# rotary_breakout.net
KiCad netlist of a schematic drawn in EAGLE
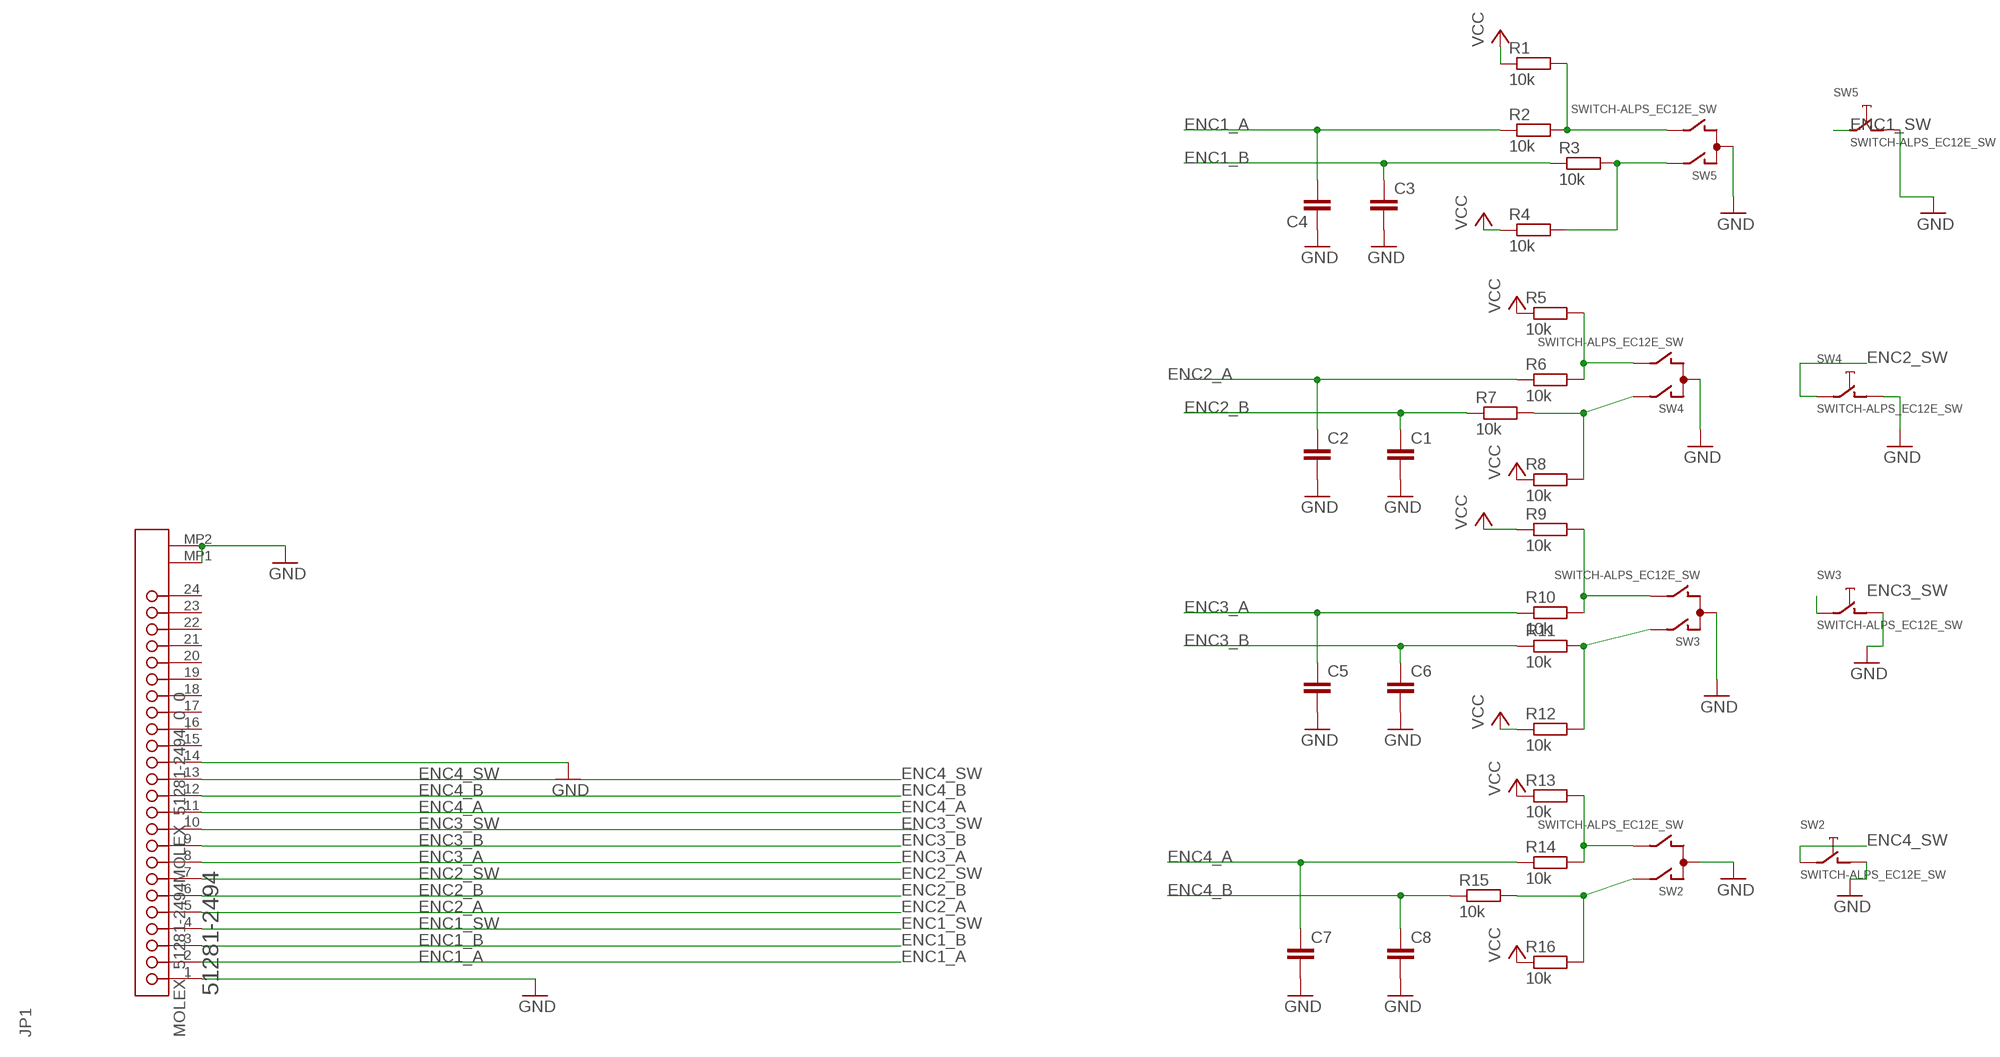
[diagram p0: schematic, sheet 1]

(export (version "E")
  (design (tool "Eeschema 10.0.6"))
  (components
    (comp (ref "C1")
      (value "C-EUC0805")
      (footprint "eagle-import:C0805")
      (libsource (lib "eagle-import") (part "C-EUC0805"))
    )
    (comp (ref "C2")
      (value "C-EUC0805")
      (footprint "eagle-import:C0805")
      (libsource (lib "eagle-import") (part "C-EUC0805"))
    )
    (comp (ref "C3")
      (value "C-EUC0805")
      (footprint "eagle-import:C0805")
      (libsource (lib "eagle-import") (part "C-EUC0805"))
    )
    (comp (ref "C4")
      (value "C-EUC0805")
      (footprint "eagle-import:C0805")
      (libsource (lib "eagle-import") (part "C-EUC0805"))
    )
    (comp (ref "C5")
      (value "C-EUC0805")
      (footprint "eagle-import:C0805")
      (libsource (lib "eagle-import") (part "C-EUC0805"))
    )
    (comp (ref "C6")
      (value "C-EUC0805")
      (footprint "eagle-import:C0805")
      (libsource (lib "eagle-import") (part "C-EUC0805"))
    )
    (comp (ref "C7")
      (value "C-EUC0805")
      (footprint "eagle-import:C0805")
      (libsource (lib "eagle-import") (part "C-EUC0805"))
    )
    (comp (ref "C8")
      (value "C-EUC0805")
      (footprint "eagle-import:C0805")
      (libsource (lib "eagle-import") (part "C-EUC0805"))
    )
    (comp (ref "JP1")
      (value "MOLEX_51281-2494MOLEX_51281-2494_0_0")
      (footprint "eagle-import:MOLEX_51281-2494_0")
      (fields (field (name "MF") "Molex") (field (name "MPN") "51281-2494"))
      (libsource (lib "eagle-import") (part "MOLEX_51281-2494MOLEX_51281-2494_0_0"))
    )
    (comp (ref "R1")
      (value "10k")
      (footprint "eagle-import:R0603")
      (libsource (lib "eagle-import") (part "R-EU_R0603"))
    )
    (comp (ref "R2")
      (value "10k")
      (footprint "eagle-import:R0603")
      (libsource (lib "eagle-import") (part "R-EU_R0603"))
    )
    (comp (ref "R3")
      (value "10k")
      (footprint "eagle-import:R0603")
      (libsource (lib "eagle-import") (part "R-EU_R0603"))
    )
    (comp (ref "R4")
      (value "10k")
      (footprint "eagle-import:R0603")
      (libsource (lib "eagle-import") (part "R-EU_R0603"))
    )
    (comp (ref "R5")
      (value "10k")
      (footprint "eagle-import:R0603")
      (libsource (lib "eagle-import") (part "R-EU_R0603"))
    )
    (comp (ref "R6")
      (value "10k")
      (footprint "eagle-import:R0603")
      (libsource (lib "eagle-import") (part "R-EU_R0603"))
    )
    (comp (ref "R7")
      (value "10k")
      (footprint "eagle-import:R0603")
      (libsource (lib "eagle-import") (part "R-EU_R0603"))
    )
    (comp (ref "R8")
      (value "10k")
      (footprint "eagle-import:R0603")
      (libsource (lib "eagle-import") (part "R-EU_R0603"))
    )
    (comp (ref "R9")
      (value "10k")
      (footprint "eagle-import:R0603")
      (libsource (lib "eagle-import") (part "R-EU_R0603"))
    )
    (comp (ref "R10")
      (value "10k")
      (footprint "eagle-import:R0603")
      (libsource (lib "eagle-import") (part "R-EU_R0603"))
    )
    (comp (ref "R11")
      (value "10k")
      (footprint "eagle-import:R0603")
      (libsource (lib "eagle-import") (part "R-EU_R0603"))
    )
    (comp (ref "R12")
      (value "10k")
      (footprint "eagle-import:R0603")
      (libsource (lib "eagle-import") (part "R-EU_R0603"))
    )
    (comp (ref "R13")
      (value "10k")
      (footprint "eagle-import:R0603")
      (libsource (lib "eagle-import") (part "R-EU_R0603"))
    )
    (comp (ref "R14")
      (value "10k")
      (footprint "eagle-import:R0603")
      (libsource (lib "eagle-import") (part "R-EU_R0603"))
    )
    (comp (ref "R15")
      (value "10k")
      (footprint "eagle-import:R0603")
      (libsource (lib "eagle-import") (part "R-EU_R0603"))
    )
    (comp (ref "R16")
      (value "10k")
      (footprint "eagle-import:R0603")
      (libsource (lib "eagle-import") (part "R-EU_R0603"))
    )
    (comp (ref "SW2")
      (value "SWITCH-ALPS_EC12E_SW")
      (footprint "eagle-import:SWITCH-ALPS_ALPS_EC12E_SW")
      (fields (field (name "MPN") "EC12E2424407"))
      (libsource (lib "eagle-import") (part "SWITCH-ALPS_EC12E_SW"))
    )
    (comp (ref "SW3")
      (value "SWITCH-ALPS_EC12E_SW")
      (footprint "eagle-import:SWITCH-ALPS_ALPS_EC12E_SW")
      (fields (field (name "MPN") "EC12E2424407"))
      (libsource (lib "eagle-import") (part "SWITCH-ALPS_EC12E_SW"))
    )
    (comp (ref "SW4")
      (value "SWITCH-ALPS_EC12E_SW")
      (footprint "eagle-import:SWITCH-ALPS_ALPS_EC12E_SW")
      (fields (field (name "MPN") "EC12E2424407"))
      (libsource (lib "eagle-import") (part "SWITCH-ALPS_EC12E_SW"))
    )
    (comp (ref "SW5")
      (value "SWITCH-ALPS_EC12E_SW")
      (footprint "eagle-import:SWITCH-ALPS_ALPS_EC12E_SW")
      (fields (field (name "MPN") "EC12E2424407"))
      (libsource (lib "eagle-import") (part "SWITCH-ALPS_EC12E_SW"))
    )
  )
  (nets
    (net (code "1") (name "/ENC1_A") (class "Default")
      (node (ref "C4") (pin "2") (pinfunction "2_2") (pintype "passive"))
      (node (ref "JP1") (pin "2") (pinfunction "2_2") (pintype "passive"))
      (node (ref "R2") (pin "1") (pinfunction "1_1") (pintype "passive"))
    )
    (net (code "2") (name "/ENC1_B") (class "Default")
      (node (ref "C3") (pin "1") (pinfunction "1_1") (pintype "passive"))
      (node (ref "JP1") (pin "3") (pinfunction "3_3") (pintype "passive"))
      (node (ref "R3") (pin "1") (pinfunction "1_1") (pintype "passive"))
    )
    (net (code "3") (name "/ENC1_SW") (class "Default")
      (node (ref "JP1") (pin "4") (pinfunction "4_4") (pintype "passive"))
      (node (ref "SW5") (pin "E") (pinfunction "2_E") (pintype "passive"))
    )
    (net (code "4") (name "/ENC2_A") (class "Default")
      (node (ref "C2") (pin "1") (pinfunction "1_1") (pintype "passive"))
      (node (ref "JP1") (pin "5") (pinfunction "5_5") (pintype "passive"))
      (node (ref "R6") (pin "1") (pinfunction "1_1") (pintype "passive"))
    )
    (net (code "5") (name "/ENC2_B") (class "Default")
      (node (ref "C1") (pin "1") (pinfunction "1_1") (pintype "passive"))
      (node (ref "JP1") (pin "6") (pinfunction "6_6") (pintype "passive"))
      (node (ref "R7") (pin "1") (pinfunction "1_1") (pintype "passive"))
    )
    (net (code "6") (name "/ENC2_SW") (class "Default")
      (node (ref "JP1") (pin "7") (pinfunction "7_7") (pintype "passive"))
      (node (ref "SW4") (pin "E") (pinfunction "2_E") (pintype "passive"))
    )
    (net (code "7") (name "/ENC3_A") (class "Default")
      (node (ref "C5") (pin "1") (pinfunction "1_1") (pintype "passive"))
      (node (ref "JP1") (pin "8") (pinfunction "8_8") (pintype "passive"))
      (node (ref "R10") (pin "1") (pinfunction "1_1") (pintype "passive"))
    )
    (net (code "8") (name "/ENC3_B") (class "Default")
      (node (ref "C6") (pin "1") (pinfunction "1_1") (pintype "passive"))
      (node (ref "JP1") (pin "9") (pinfunction "9_9") (pintype "passive"))
      (node (ref "R11") (pin "1") (pinfunction "1_1") (pintype "passive"))
    )
    (net (code "9") (name "/ENC3_SW") (class "Default")
      (node (ref "JP1") (pin "10") (pinfunction "10_10") (pintype "passive"))
      (node (ref "SW3") (pin "E") (pinfunction "2_E") (pintype "passive"))
    )
    (net (code "10") (name "/ENC4_A") (class "Default")
      (node (ref "C7") (pin "1") (pinfunction "1_1") (pintype "passive"))
      (node (ref "JP1") (pin "11") (pinfunction "11_11") (pintype "passive"))
      (node (ref "R14") (pin "1") (pinfunction "1_1") (pintype "passive"))
    )
    (net (code "11") (name "/ENC4_B") (class "Default")
      (node (ref "C8") (pin "1") (pinfunction "1_1") (pintype "passive"))
      (node (ref "JP1") (pin "12") (pinfunction "12_12") (pintype "passive"))
      (node (ref "R15") (pin "1") (pinfunction "1_1") (pintype "passive"))
    )
    (net (code "12") (name "/ENC4_SW") (class "Default")
      (node (ref "JP1") (pin "13") (pinfunction "13_13") (pintype "passive"))
      (node (ref "SW2") (pin "E") (pinfunction "2_E") (pintype "passive"))
    )
    (net (code "13") (name "GND") (class "Default")
      (node (ref "C1") (pin "2") (pinfunction "2_2") (pintype "passive"))
      (node (ref "C2") (pin "2") (pinfunction "2_2") (pintype "passive"))
      (node (ref "C3") (pin "2") (pinfunction "2_2") (pintype "passive"))
      (node (ref "C4") (pin "1") (pinfunction "1_1") (pintype "passive"))
      (node (ref "C5") (pin "2") (pinfunction "2_2") (pintype "passive"))
      (node (ref "C6") (pin "2") (pinfunction "2_2") (pintype "passive"))
      (node (ref "C7") (pin "2") (pinfunction "2_2") (pintype "passive"))
      (node (ref "C8") (pin "2") (pinfunction "2_2") (pintype "passive"))
      (node (ref "JP1") (pin "1") (pinfunction "1_1") (pintype "passive"))
      (node (ref "JP1") (pin "14") (pinfunction "14_14") (pintype "passive"))
      (node (ref "JP1") (pin "MP1") (pinfunction "MP1_MP1") (pintype "passive"))
      (node (ref "JP1") (pin "MP2") (pinfunction "MP2_MP2") (pintype "passive"))
      (node (ref "SW2") (pin "C") (pinfunction "C_C") (pintype "passive"))
      (node (ref "SW2") (pin "D") (pinfunction "1_D") (pintype "passive"))
      (node (ref "SW3") (pin "C") (pinfunction "C_C") (pintype "passive"))
      (node (ref "SW3") (pin "D") (pinfunction "1_D") (pintype "passive"))
      (node (ref "SW4") (pin "C") (pinfunction "C_C") (pintype "passive"))
      (node (ref "SW4") (pin "D") (pinfunction "1_D") (pintype "passive"))
      (node (ref "SW5") (pin "C") (pinfunction "C_C") (pintype "passive"))
      (node (ref "SW5") (pin "D") (pinfunction "1_D") (pintype "passive"))
    )
    (net (code "14") (name "Net-(R1-Pad2)") (class "Default")
      (node (ref "R1") (pin "2") (pinfunction "2_2") (pintype "passive"))
      (node (ref "R2") (pin "2") (pinfunction "2_2") (pintype "passive"))
      (node (ref "SW5") (pin "B") (pinfunction "B_B") (pintype "passive"))
    )
    (net (code "15") (name "Net-(R3-Pad2)") (class "Default")
      (node (ref "R3") (pin "2") (pinfunction "2_2") (pintype "passive"))
      (node (ref "R4") (pin "2") (pinfunction "2_2") (pintype "passive"))
      (node (ref "SW5") (pin "A") (pinfunction "A_A") (pintype "passive"))
    )
    (net (code "16") (name "Net-(R5-Pad2)") (class "Default")
      (node (ref "R5") (pin "2") (pinfunction "2_2") (pintype "passive"))
      (node (ref "R6") (pin "2") (pinfunction "2_2") (pintype "passive"))
      (node (ref "SW4") (pin "B") (pinfunction "B_B") (pintype "passive"))
    )
    (net (code "17") (name "Net-(R7-Pad2)") (class "Default")
      (node (ref "R7") (pin "2") (pinfunction "2_2") (pintype "passive"))
      (node (ref "R8") (pin "2") (pinfunction "2_2") (pintype "passive"))
      (node (ref "SW4") (pin "A") (pinfunction "A_A") (pintype "passive"))
    )
    (net (code "18") (name "Net-(R10-Pad2)") (class "Default")
      (node (ref "R10") (pin "2") (pinfunction "2_2") (pintype "passive"))
      (node (ref "R9") (pin "2") (pinfunction "2_2") (pintype "passive"))
      (node (ref "SW3") (pin "B") (pinfunction "B_B") (pintype "passive"))
    )
    (net (code "19") (name "Net-(R11-Pad2)") (class "Default")
      (node (ref "R11") (pin "2") (pinfunction "2_2") (pintype "passive"))
      (node (ref "R12") (pin "2") (pinfunction "2_2") (pintype "passive"))
      (node (ref "SW3") (pin "A") (pinfunction "A_A") (pintype "passive"))
    )
    (net (code "20") (name "Net-(R13-Pad2)") (class "Default")
      (node (ref "R13") (pin "2") (pinfunction "2_2") (pintype "passive"))
      (node (ref "R14") (pin "2") (pinfunction "2_2") (pintype "passive"))
      (node (ref "SW2") (pin "B") (pinfunction "B_B") (pintype "passive"))
    )
    (net (code "21") (name "Net-(R15-Pad2)") (class "Default")
      (node (ref "R15") (pin "2") (pinfunction "2_2") (pintype "passive"))
      (node (ref "R16") (pin "2") (pinfunction "2_2") (pintype "passive"))
      (node (ref "SW2") (pin "A") (pinfunction "A_A") (pintype "passive"))
    )
    (net (code "22") (name "VCC") (class "Default")
      (node (ref "R1") (pin "1") (pinfunction "1_1") (pintype "passive"))
      (node (ref "R12") (pin "1") (pinfunction "1_1") (pintype "passive"))
      (node (ref "R13") (pin "1") (pinfunction "1_1") (pintype "passive"))
      (node (ref "R16") (pin "1") (pinfunction "1_1") (pintype "passive"))
      (node (ref "R4") (pin "1") (pinfunction "1_1") (pintype "passive"))
      (node (ref "R5") (pin "1") (pinfunction "1_1") (pintype "passive"))
      (node (ref "R8") (pin "1") (pinfunction "1_1") (pintype "passive"))
      (node (ref "R9") (pin "1") (pinfunction "1_1") (pintype "passive"))
    )
    (net (code "23") (name "unconnected-(JP1-Pad15)") (class "Default")
      (node (ref "JP1") (pin "15") (pinfunction "15_15") (pintype "passive"))
    )
    (net (code "24") (name "unconnected-(JP1-Pad16)") (class "Default")
      (node (ref "JP1") (pin "16") (pinfunction "16_16") (pintype "passive"))
    )
    (net (code "25") (name "unconnected-(JP1-Pad17)") (class "Default")
      (node (ref "JP1") (pin "17") (pinfunction "17_17") (pintype "passive"))
    )
    (net (code "26") (name "unconnected-(JP1-Pad18)") (class "Default")
      (node (ref "JP1") (pin "18") (pinfunction "18_18") (pintype "passive"))
    )
    (net (code "27") (name "unconnected-(JP1-Pad19)") (class "Default")
      (node (ref "JP1") (pin "19") (pinfunction "19_19") (pintype "passive"))
    )
    (net (code "28") (name "unconnected-(JP1-Pad20)") (class "Default")
      (node (ref "JP1") (pin "20") (pinfunction "20_20") (pintype "passive"))
    )
    (net (code "29") (name "unconnected-(JP1-Pad21)") (class "Default")
      (node (ref "JP1") (pin "21") (pinfunction "21_21") (pintype "passive"))
    )
    (net (code "30") (name "unconnected-(JP1-Pad22)") (class "Default")
      (node (ref "JP1") (pin "22") (pinfunction "22_22") (pintype "passive"))
    )
    (net (code "31") (name "unconnected-(JP1-Pad23)") (class "Default")
      (node (ref "JP1") (pin "23") (pinfunction "23_23") (pintype "passive"))
    )
    (net (code "32") (name "unconnected-(JP1-Pad24)") (class "Default")
      (node (ref "JP1") (pin "24") (pinfunction "24_24") (pintype "passive"))
    )
  )
)
